# Registers.net
KiCad netlist of a schematic drawn in EAGLE
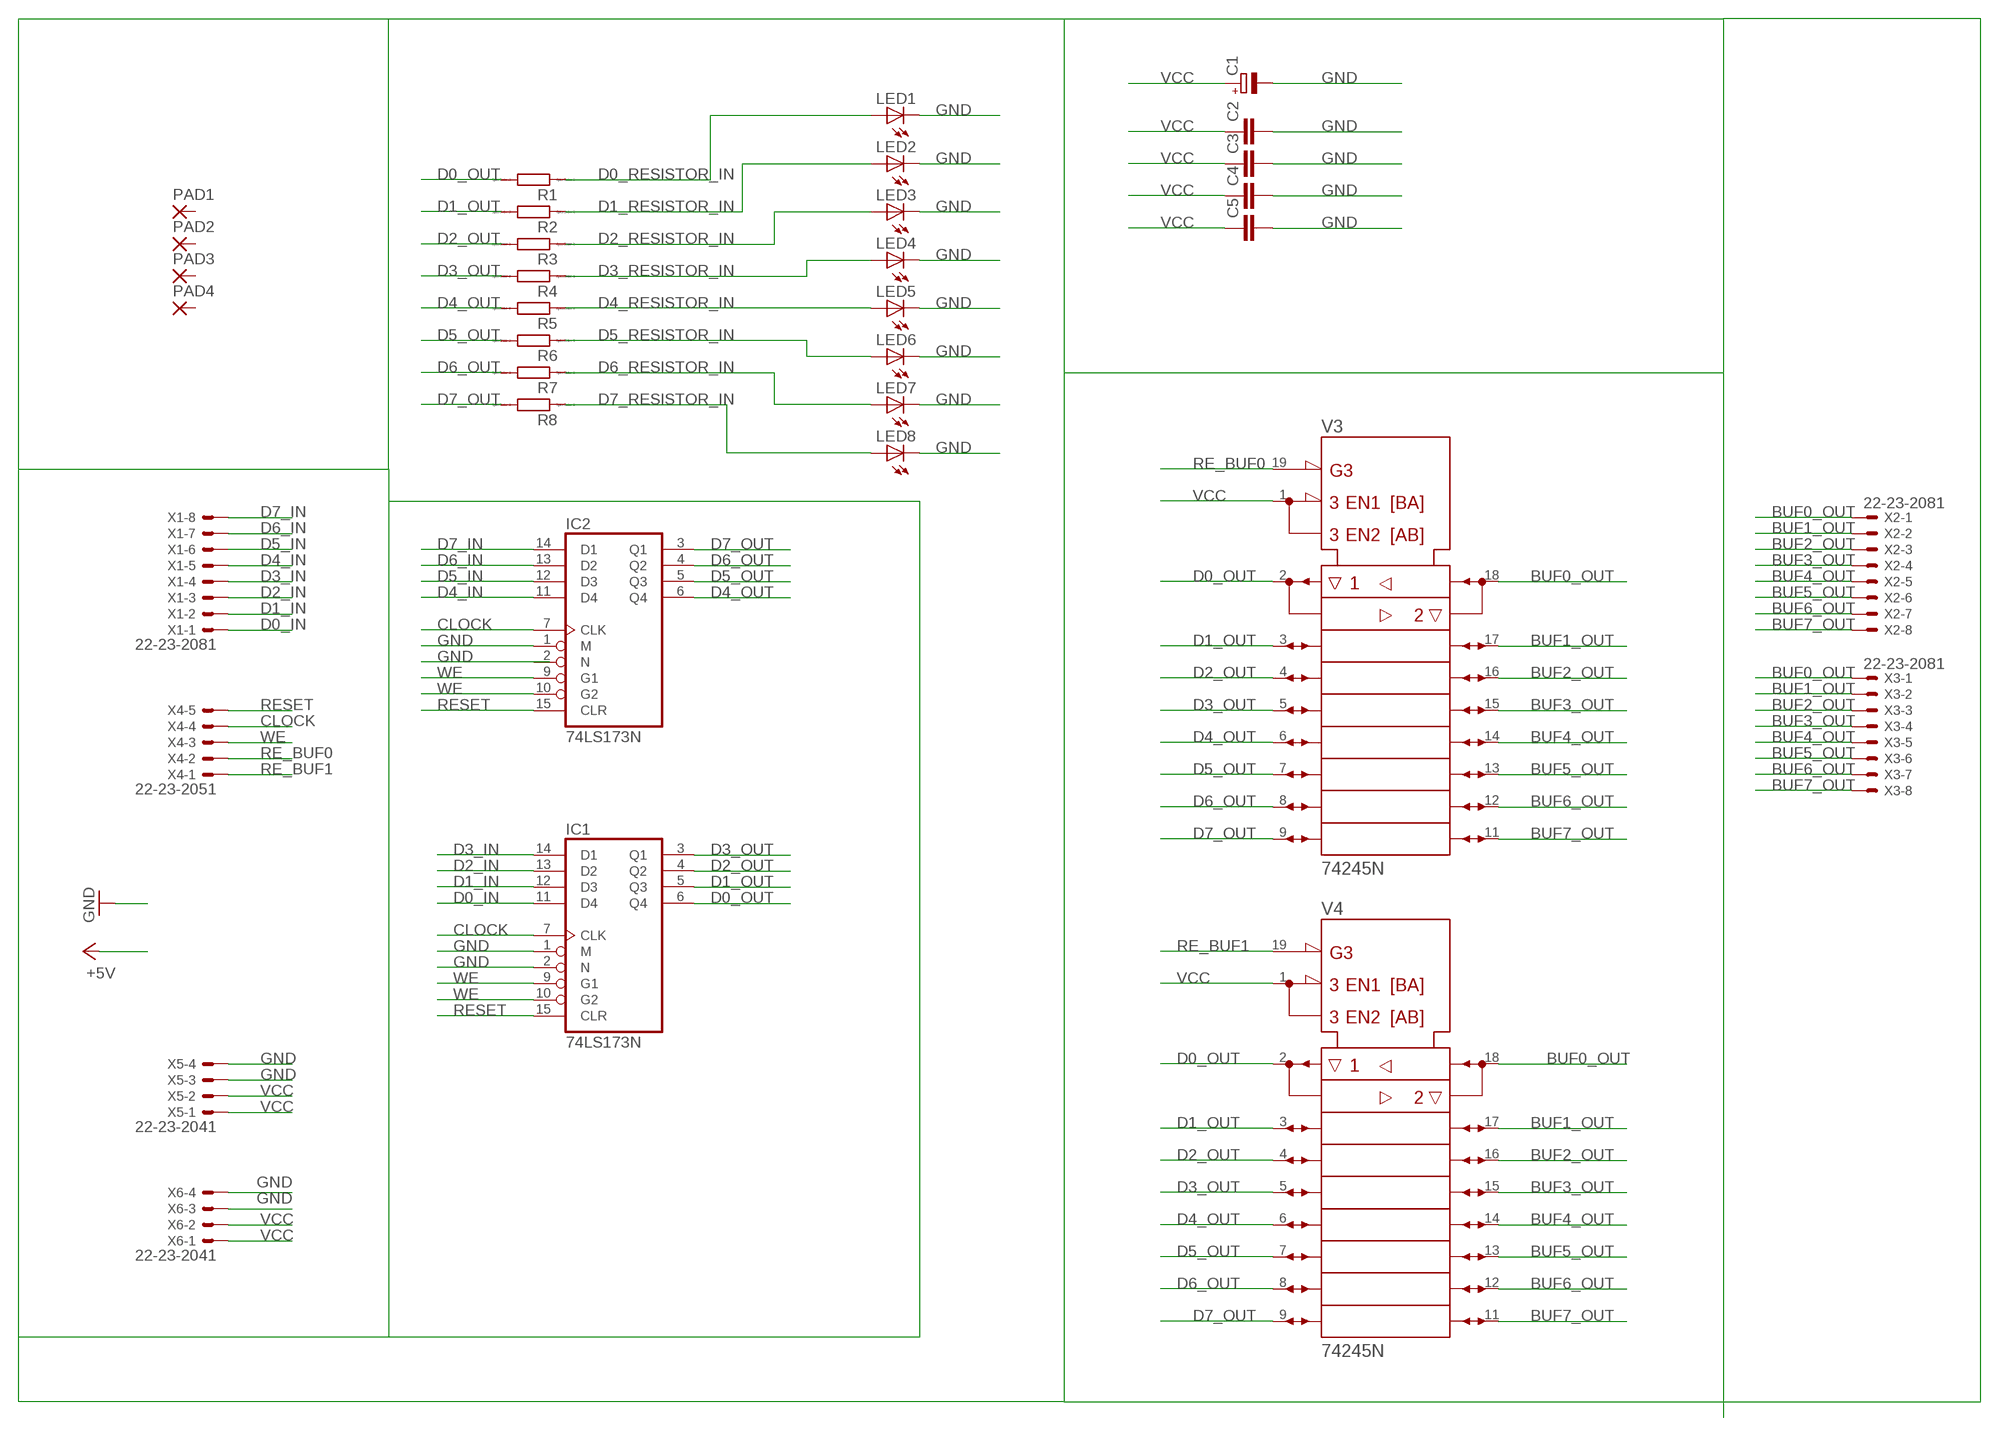
[diagram p0: schematic, sheet 1]

(export (version "E")
  (design (tool "Eeschema 10.0.6"))
  (components
    (comp (ref "C1")
      (value "CPOL-EUE2.5-6")
      (footprint "eagle-import:E2,5-6")
      (libsource (lib "eagle-import") (part "CPOL-EUE2.5-6"))
    )
    (comp (ref "C2")
      (value "C-EU025-025X050")
      (footprint "eagle-import:C025-025X050")
      (libsource (lib "eagle-import") (part "C-EU025-025X050"))
    )
    (comp (ref "C3")
      (value "C-EU025-025X050")
      (footprint "eagle-import:C025-025X050")
      (libsource (lib "eagle-import") (part "C-EU025-025X050"))
    )
    (comp (ref "C4")
      (value "C-EU025-025X050")
      (footprint "eagle-import:C025-025X050")
      (libsource (lib "eagle-import") (part "C-EU025-025X050"))
    )
    (comp (ref "C5")
      (value "C-EU025-025X050")
      (footprint "eagle-import:C025-025X050")
      (libsource (lib "eagle-import") (part "C-EU025-025X050"))
    )
    (comp (ref "IC1")
      (value "74LS173N")
      (footprint "eagle-import:DIL16")
      (libsource (lib "eagle-import") (part "74173NLS"))
    )
    (comp (ref "IC2")
      (value "74LS173N")
      (footprint "eagle-import:DIL16")
      (libsource (lib "eagle-import") (part "74173NLS"))
    )
    (comp (ref "LED1")
      (value "LED5MM")
      (footprint "eagle-import:LED5MM")
      (libsource (lib "eagle-import") (part "LED5MM"))
    )
    (comp (ref "LED2")
      (value "LED5MM")
      (footprint "eagle-import:LED5MM")
      (libsource (lib "eagle-import") (part "LED5MM"))
    )
    (comp (ref "LED3")
      (value "LED5MM")
      (footprint "eagle-import:LED5MM")
      (libsource (lib "eagle-import") (part "LED5MM"))
    )
    (comp (ref "LED4")
      (value "LED5MM")
      (footprint "eagle-import:LED5MM")
      (libsource (lib "eagle-import") (part "LED5MM"))
    )
    (comp (ref "LED5")
      (value "LED5MM")
      (footprint "eagle-import:LED5MM")
      (libsource (lib "eagle-import") (part "LED5MM"))
    )
    (comp (ref "LED6")
      (value "LED5MM")
      (footprint "eagle-import:LED5MM")
      (libsource (lib "eagle-import") (part "LED5MM"))
    )
    (comp (ref "LED7")
      (value "LED5MM")
      (footprint "eagle-import:LED5MM")
      (libsource (lib "eagle-import") (part "LED5MM"))
    )
    (comp (ref "LED8")
      (value "LED5MM")
      (footprint "eagle-import:LED5MM")
      (libsource (lib "eagle-import") (part "LED5MM"))
    )
    (comp (ref "PAD1")
      (value "2,54/1,1")
      (footprint "eagle-import:2,54_1,1")
      (libsource (lib "eagle-import") (part "2,54/1,1"))
    )
    (comp (ref "PAD2")
      (value "2,54/1,1")
      (footprint "eagle-import:2,54_1,1")
      (libsource (lib "eagle-import") (part "2,54/1,1"))
    )
    (comp (ref "PAD3")
      (value "2,54/1,1")
      (footprint "eagle-import:2,54_1,1")
      (libsource (lib "eagle-import") (part "2,54/1,1"))
    )
    (comp (ref "PAD4")
      (value "2,54/1,1")
      (footprint "eagle-import:2,54_1,1")
      (libsource (lib "eagle-import") (part "2,54/1,1"))
    )
    (comp (ref "R1")
      (value "R0207/10")
      (footprint "eagle-import:0207_10")
      (libsource (lib "eagle-import") (part "R0207/10"))
    )
    (comp (ref "R2")
      (value "R0207/10")
      (footprint "eagle-import:0207_10")
      (libsource (lib "eagle-import") (part "R0207/10"))
    )
    (comp (ref "R3")
      (value "R0207/10")
      (footprint "eagle-import:0207_10")
      (libsource (lib "eagle-import") (part "R0207/10"))
    )
    (comp (ref "R4")
      (value "R0207/10")
      (footprint "eagle-import:0207_10")
      (libsource (lib "eagle-import") (part "R0207/10"))
    )
    (comp (ref "R5")
      (value "R0207/10")
      (footprint "eagle-import:0207_10")
      (libsource (lib "eagle-import") (part "R0207/10"))
    )
    (comp (ref "R6")
      (value "R0207/10")
      (footprint "eagle-import:0207_10")
      (libsource (lib "eagle-import") (part "R0207/10"))
    )
    (comp (ref "R7")
      (value "R0207/10")
      (footprint "eagle-import:0207_10")
      (libsource (lib "eagle-import") (part "R0207/10"))
    )
    (comp (ref "R8")
      (value "R0207/10")
      (footprint "eagle-import:0207_10")
      (libsource (lib "eagle-import") (part "R0207/10"))
    )
    (comp (ref "V3")
      (value "74245N")
      (footprint "eagle-import:DIL20")
      (libsource (lib "eagle-import") (part "74245N"))
    )
    (comp (ref "V4")
      (value "74245N")
      (footprint "eagle-import:DIL20")
      (libsource (lib "eagle-import") (part "74245N"))
    )
    (comp (ref "X1")
      (value "22-23-2081")
      (footprint "eagle-import:22-23-2081")
      (fields (field (name "MF") "MOLEX"))
      (libsource (lib "eagle-import") (part "22-23-2081"))
    )
    (comp (ref "X2")
      (value "22-23-2081")
      (footprint "eagle-import:22-23-2081")
      (fields (field (name "MF") "MOLEX"))
      (libsource (lib "eagle-import") (part "22-23-2081"))
    )
    (comp (ref "X3")
      (value "22-23-2081")
      (footprint "eagle-import:22-23-2081")
      (fields (field (name "MF") "MOLEX"))
      (libsource (lib "eagle-import") (part "22-23-2081"))
    )
    (comp (ref "X4")
      (value "22-23-2051")
      (footprint "eagle-import:22-23-2051")
      (fields (field (name "MF") "MOLEX"))
      (libsource (lib "eagle-import") (part "22-23-2051"))
    )
    (comp (ref "X5")
      (value "22-23-2041")
      (footprint "eagle-import:22-23-2041")
      (fields (field (name "MF") "MOLEX"))
      (libsource (lib "eagle-import") (part "22-23-2041"))
    )
    (comp (ref "X6")
      (value "22-23-2041")
      (footprint "eagle-import:22-23-2041")
      (fields (field (name "MF") "MOLEX"))
      (libsource (lib "eagle-import") (part "22-23-2041"))
    )
  )
  (nets
    (net (code "2") (name "/BUF0_OUT") (class "Default")
      (node (ref "V3") (pin "18") (pinfunction "B1_18") (pintype "bidirectional"))
      (node (ref "V4") (pin "18") (pinfunction "B1_18") (pintype "bidirectional"))
      (node (ref "X2") (pin "1") (pinfunction "S_1") (pintype "passive"))
      (node (ref "X3") (pin "1") (pinfunction "S_1") (pintype "passive"))
    )
    (net (code "3") (name "/BUF1_OUT") (class "Default")
      (node (ref "V3") (pin "17") (pinfunction "B2_17") (pintype "bidirectional"))
      (node (ref "V4") (pin "17") (pinfunction "B2_17") (pintype "bidirectional"))
      (node (ref "X2") (pin "2") (pinfunction "S_2") (pintype "passive"))
      (node (ref "X3") (pin "2") (pinfunction "S_2") (pintype "passive"))
    )
    (net (code "4") (name "/BUF2_OUT") (class "Default")
      (node (ref "V3") (pin "16") (pinfunction "B3_16") (pintype "bidirectional"))
      (node (ref "V4") (pin "16") (pinfunction "B3_16") (pintype "bidirectional"))
      (node (ref "X2") (pin "3") (pinfunction "S_3") (pintype "passive"))
      (node (ref "X3") (pin "3") (pinfunction "S_3") (pintype "passive"))
    )
    (net (code "5") (name "/BUF3_OUT") (class "Default")
      (node (ref "V3") (pin "15") (pinfunction "B4_15") (pintype "bidirectional"))
      (node (ref "V4") (pin "15") (pinfunction "B4_15") (pintype "bidirectional"))
      (node (ref "X2") (pin "4") (pinfunction "S_4") (pintype "passive"))
      (node (ref "X3") (pin "4") (pinfunction "S_4") (pintype "passive"))
    )
    (net (code "6") (name "/BUF4_OUT") (class "Default")
      (node (ref "V3") (pin "14") (pinfunction "B5_14") (pintype "bidirectional"))
      (node (ref "V4") (pin "14") (pinfunction "B5_14") (pintype "bidirectional"))
      (node (ref "X2") (pin "5") (pinfunction "S_5") (pintype "passive"))
      (node (ref "X3") (pin "5") (pinfunction "S_5") (pintype "passive"))
    )
    (net (code "7") (name "/BUF5_OUT") (class "Default")
      (node (ref "V3") (pin "13") (pinfunction "B6_13") (pintype "bidirectional"))
      (node (ref "V4") (pin "13") (pinfunction "B6_13") (pintype "bidirectional"))
      (node (ref "X2") (pin "6") (pinfunction "S_6") (pintype "passive"))
      (node (ref "X3") (pin "6") (pinfunction "S_6") (pintype "passive"))
    )
    (net (code "8") (name "/BUF6_OUT") (class "Default")
      (node (ref "V3") (pin "12") (pinfunction "B7_12") (pintype "bidirectional"))
      (node (ref "V4") (pin "12") (pinfunction "B7_12") (pintype "bidirectional"))
      (node (ref "X2") (pin "7") (pinfunction "S_7") (pintype "passive"))
      (node (ref "X3") (pin "7") (pinfunction "S_7") (pintype "passive"))
    )
    (net (code "9") (name "/BUF7_OUT") (class "Default")
      (node (ref "V3") (pin "11") (pinfunction "B8_11") (pintype "bidirectional"))
      (node (ref "V4") (pin "11") (pinfunction "B8_11") (pintype "bidirectional"))
      (node (ref "X2") (pin "8") (pinfunction "S_8") (pintype "passive"))
      (node (ref "X3") (pin "8") (pinfunction "S_8") (pintype "passive"))
    )
    (net (code "10") (name "/CLOCK") (class "Default")
      (node (ref "IC1") (pin "7") (pinfunction "CLK_7") (pintype "input"))
      (node (ref "IC2") (pin "7") (pinfunction "CLK_7") (pintype "input"))
      (node (ref "X4") (pin "4") (pinfunction "S_4") (pintype "passive"))
    )
    (net (code "11") (name "/D0_IN") (class "Default")
      (node (ref "IC1") (pin "11") (pinfunction "D4_11") (pintype "input"))
      (node (ref "X1") (pin "1") (pinfunction "S_1") (pintype "passive"))
    )
    (net (code "12") (name "/D0_OUT") (class "Default")
      (node (ref "IC1") (pin "6") (pinfunction "Q4_6") (pintype "tri_state"))
      (node (ref "R1") (pin "2") (pinfunction "2_2") (pintype "passive"))
      (node (ref "V3") (pin "2") (pinfunction "A1_2") (pintype "bidirectional"))
      (node (ref "V4") (pin "2") (pinfunction "A1_2") (pintype "bidirectional"))
    )
    (net (code "13") (name "/D0_RESISTOR_IN") (class "Default")
      (node (ref "LED1") (pin "A") (pinfunction "A_A") (pintype "passive"))
      (node (ref "R1") (pin "1") (pinfunction "1_1") (pintype "passive"))
    )
    (net (code "14") (name "/D1_IN") (class "Default")
      (node (ref "IC1") (pin "12") (pinfunction "D3_12") (pintype "input"))
      (node (ref "X1") (pin "2") (pinfunction "S_2") (pintype "passive"))
    )
    (net (code "15") (name "/D1_OUT") (class "Default")
      (node (ref "IC1") (pin "5") (pinfunction "Q3_5") (pintype "tri_state"))
      (node (ref "R2") (pin "2") (pinfunction "2_2") (pintype "passive"))
      (node (ref "V3") (pin "3") (pinfunction "A2_3") (pintype "bidirectional"))
      (node (ref "V4") (pin "3") (pinfunction "A2_3") (pintype "bidirectional"))
    )
    (net (code "16") (name "/D1_RESISTOR_IN") (class "Default")
      (node (ref "LED2") (pin "A") (pinfunction "A_A") (pintype "passive"))
      (node (ref "R2") (pin "1") (pinfunction "1_1") (pintype "passive"))
    )
    (net (code "17") (name "/D2_IN") (class "Default")
      (node (ref "IC1") (pin "13") (pinfunction "D2_13") (pintype "input"))
      (node (ref "X1") (pin "3") (pinfunction "S_3") (pintype "passive"))
    )
    (net (code "18") (name "/D2_OUT") (class "Default")
      (node (ref "IC1") (pin "4") (pinfunction "Q2_4") (pintype "tri_state"))
      (node (ref "R3") (pin "2") (pinfunction "2_2") (pintype "passive"))
      (node (ref "V3") (pin "4") (pinfunction "A3_4") (pintype "bidirectional"))
      (node (ref "V4") (pin "4") (pinfunction "A3_4") (pintype "bidirectional"))
    )
    (net (code "19") (name "/D2_RESISTOR_IN") (class "Default")
      (node (ref "LED3") (pin "A") (pinfunction "A_A") (pintype "passive"))
      (node (ref "R3") (pin "1") (pinfunction "1_1") (pintype "passive"))
    )
    (net (code "20") (name "/D3_IN") (class "Default")
      (node (ref "IC1") (pin "14") (pinfunction "D1_14") (pintype "input"))
      (node (ref "X1") (pin "4") (pinfunction "S_4") (pintype "passive"))
    )
    (net (code "21") (name "/D3_OUT") (class "Default")
      (node (ref "IC1") (pin "3") (pinfunction "Q1_3") (pintype "tri_state"))
      (node (ref "R4") (pin "2") (pinfunction "2_2") (pintype "passive"))
      (node (ref "V3") (pin "5") (pinfunction "A4_5") (pintype "bidirectional"))
      (node (ref "V4") (pin "5") (pinfunction "A4_5") (pintype "bidirectional"))
    )
    (net (code "22") (name "/D3_RESISTOR_IN") (class "Default")
      (node (ref "LED4") (pin "A") (pinfunction "A_A") (pintype "passive"))
      (node (ref "R4") (pin "1") (pinfunction "1_1") (pintype "passive"))
    )
    (net (code "23") (name "/D4_IN") (class "Default")
      (node (ref "IC2") (pin "11") (pinfunction "D4_11") (pintype "input"))
      (node (ref "X1") (pin "5") (pinfunction "S_5") (pintype "passive"))
    )
    (net (code "24") (name "/D4_OUT") (class "Default")
      (node (ref "IC2") (pin "6") (pinfunction "Q4_6") (pintype "tri_state"))
      (node (ref "R5") (pin "2") (pinfunction "2_2") (pintype "passive"))
      (node (ref "V3") (pin "6") (pinfunction "A5_6") (pintype "bidirectional"))
      (node (ref "V4") (pin "6") (pinfunction "A5_6") (pintype "bidirectional"))
    )
    (net (code "25") (name "/D4_RESISTOR_IN") (class "Default")
      (node (ref "LED5") (pin "A") (pinfunction "A_A") (pintype "passive"))
      (node (ref "R5") (pin "1") (pinfunction "1_1") (pintype "passive"))
    )
    (net (code "26") (name "/D5_IN") (class "Default")
      (node (ref "IC2") (pin "12") (pinfunction "D3_12") (pintype "input"))
      (node (ref "X1") (pin "6") (pinfunction "S_6") (pintype "passive"))
    )
    (net (code "27") (name "/D5_OUT") (class "Default")
      (node (ref "IC2") (pin "5") (pinfunction "Q3_5") (pintype "tri_state"))
      (node (ref "R6") (pin "2") (pinfunction "2_2") (pintype "passive"))
      (node (ref "V3") (pin "7") (pinfunction "A6_7") (pintype "bidirectional"))
      (node (ref "V4") (pin "7") (pinfunction "A6_7") (pintype "bidirectional"))
    )
    (net (code "28") (name "/D5_RESISTOR_IN") (class "Default")
      (node (ref "LED6") (pin "A") (pinfunction "A_A") (pintype "passive"))
      (node (ref "R6") (pin "1") (pinfunction "1_1") (pintype "passive"))
    )
    (net (code "29") (name "/D6_IN") (class "Default")
      (node (ref "IC2") (pin "13") (pinfunction "D2_13") (pintype "input"))
      (node (ref "X1") (pin "7") (pinfunction "S_7") (pintype "passive"))
    )
    (net (code "30") (name "/D6_OUT") (class "Default")
      (node (ref "IC2") (pin "4") (pinfunction "Q2_4") (pintype "tri_state"))
      (node (ref "R7") (pin "2") (pinfunction "2_2") (pintype "passive"))
      (node (ref "V3") (pin "8") (pinfunction "A7_8") (pintype "bidirectional"))
      (node (ref "V4") (pin "8") (pinfunction "A7_8") (pintype "bidirectional"))
    )
    (net (code "31") (name "/D6_RESISTOR_IN") (class "Default")
      (node (ref "LED7") (pin "A") (pinfunction "A_A") (pintype "passive"))
      (node (ref "R7") (pin "1") (pinfunction "1_1") (pintype "passive"))
    )
    (net (code "32") (name "/D7_IN") (class "Default")
      (node (ref "IC2") (pin "14") (pinfunction "D1_14") (pintype "input"))
      (node (ref "X1") (pin "8") (pinfunction "S_8") (pintype "passive"))
    )
    (net (code "33") (name "/D7_OUT") (class "Default")
      (node (ref "IC2") (pin "3") (pinfunction "Q1_3") (pintype "tri_state"))
      (node (ref "R8") (pin "2") (pinfunction "2_2") (pintype "passive"))
      (node (ref "V3") (pin "9") (pinfunction "A8_9") (pintype "bidirectional"))
      (node (ref "V4") (pin "9") (pinfunction "A8_9") (pintype "bidirectional"))
    )
    (net (code "34") (name "/D7_RESISTOR_IN") (class "Default")
      (node (ref "LED8") (pin "A") (pinfunction "A_A") (pintype "passive"))
      (node (ref "R8") (pin "1") (pinfunction "1_1") (pintype "passive"))
    )
    (net (code "35") (name "/RESET") (class "Default")
      (node (ref "IC1") (pin "15") (pinfunction "CLR_15") (pintype "input"))
      (node (ref "IC2") (pin "15") (pinfunction "CLR_15") (pintype "input"))
      (node (ref "X4") (pin "5") (pinfunction "S_5") (pintype "passive"))
    )
    (net (code "36") (name "/RE_BUF0") (class "Default")
      (node (ref "V3") (pin "19") (pinfunction "~{G}_19") (pintype "input"))
      (node (ref "X4") (pin "2") (pinfunction "S_2") (pintype "passive"))
    )
    (net (code "37") (name "/RE_BUF1") (class "Default")
      (node (ref "V4") (pin "19") (pinfunction "~{G}_19") (pintype "input"))
      (node (ref "X4") (pin "1") (pinfunction "S_1") (pintype "passive"))
    )
    (net (code "38") (name "/VCC") (class "Default")
      (node (ref "C1") (pin "+") (pinfunction "+_+") (pintype "passive"))
      (node (ref "C2") (pin "1") (pinfunction "1_1") (pintype "passive"))
      (node (ref "C3") (pin "1") (pinfunction "1_1") (pintype "passive"))
      (node (ref "C4") (pin "1") (pinfunction "1_1") (pintype "passive"))
      (node (ref "C5") (pin "1") (pinfunction "1_1") (pintype "passive"))
      (node (ref "V3") (pin "1") (pinfunction "DIR_1") (pintype "input"))
      (node (ref "V4") (pin "1") (pinfunction "DIR_1") (pintype "input"))
      (node (ref "X5") (pin "1") (pinfunction "S_1") (pintype "passive"))
      (node (ref "X5") (pin "2") (pinfunction "S_2") (pintype "passive"))
      (node (ref "X6") (pin "1") (pinfunction "S_1") (pintype "passive"))
      (node (ref "X6") (pin "2") (pinfunction "S_2") (pintype "passive"))
    )
    (net (code "39") (name "/WE") (class "Default")
      (node (ref "IC1") (pin "10") (pinfunction "G2_10") (pintype "input"))
      (node (ref "IC1") (pin "9") (pinfunction "G1_9") (pintype "input"))
      (node (ref "IC2") (pin "10") (pinfunction "G2_10") (pintype "input"))
      (node (ref "IC2") (pin "9") (pinfunction "G1_9") (pintype "input"))
      (node (ref "X4") (pin "3") (pinfunction "S_3") (pintype "passive"))
    )
    (net (code "40") (name "GND") (class "Default")
      (node (ref "C1") (pin "-") (pinfunction "-_-") (pintype "passive"))
      (node (ref "C2") (pin "2") (pinfunction "2_2") (pintype "passive"))
      (node (ref "C3") (pin "2") (pinfunction "2_2") (pintype "passive"))
      (node (ref "C4") (pin "2") (pinfunction "2_2") (pintype "passive"))
      (node (ref "C5") (pin "2") (pinfunction "2_2") (pintype "passive"))
      (node (ref "IC1") (pin "1") (pinfunction "M_1") (pintype "input"))
      (node (ref "IC1") (pin "2") (pinfunction "N_2") (pintype "input"))
      (node (ref "IC2") (pin "1") (pinfunction "M_1") (pintype "input"))
      (node (ref "LED1") (pin "K") (pinfunction "C_K") (pintype "passive"))
      (node (ref "LED2") (pin "K") (pinfunction "C_K") (pintype "passive"))
      (node (ref "LED3") (pin "K") (pinfunction "C_K") (pintype "passive"))
      (node (ref "LED4") (pin "K") (pinfunction "C_K") (pintype "passive"))
      (node (ref "LED5") (pin "K") (pinfunction "C_K") (pintype "passive"))
      (node (ref "LED6") (pin "K") (pinfunction "C_K") (pintype "passive"))
      (node (ref "LED7") (pin "K") (pinfunction "C_K") (pintype "passive"))
      (node (ref "LED8") (pin "K") (pinfunction "C_K") (pintype "passive"))
      (node (ref "X5") (pin "3") (pinfunction "S_3") (pintype "passive"))
      (node (ref "X5") (pin "4") (pinfunction "S_4") (pintype "passive"))
      (node (ref "X6") (pin "3") (pinfunction "S_3") (pintype "passive"))
      (node (ref "X6") (pin "4") (pinfunction "S_4") (pintype "passive"))
    )
    (net (code "41") (name "unconnected-(IC2A-N-Pad2)") (class "Default")
      (node (ref "IC2") (pin "2") (pinfunction "N_2") (pintype "input"))
    )
    (net (code "42") (name "unconnected-(PAD1-P-Pad1)") (class "Default")
      (node (ref "PAD1") (pin "1") (pinfunction "P_1") (pintype "passive"))
    )
    (net (code "43") (name "unconnected-(PAD2-P-Pad1)") (class "Default")
      (node (ref "PAD2") (pin "1") (pinfunction "P_1") (pintype "passive"))
    )
    (net (code "44") (name "unconnected-(PAD3-P-Pad1)") (class "Default")
      (node (ref "PAD3") (pin "1") (pinfunction "P_1") (pintype "passive"))
    )
    (net (code "45") (name "unconnected-(PAD4-P-Pad1)") (class "Default")
      (node (ref "PAD4") (pin "1") (pinfunction "P_1") (pintype "passive"))
    )
  )
)
